# sp6641-aek.net
KiCad netlist of a schematic drawn in EAGLE
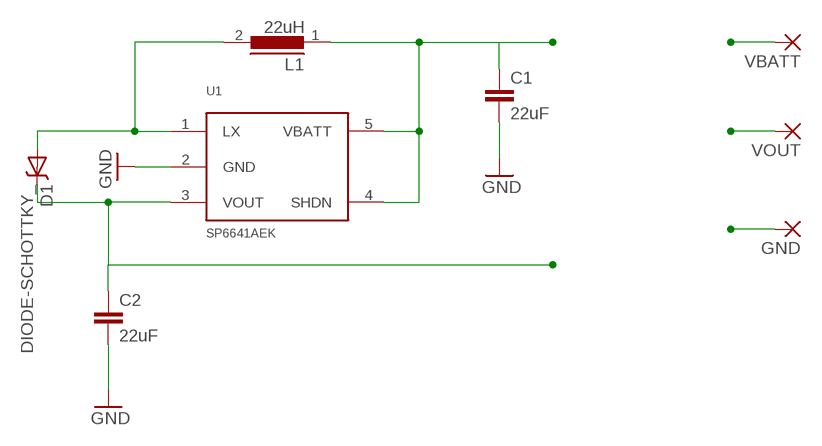
[diagram p0: schematic, sheet 1]

(export (version "E")
  (design (tool "Eeschema 10.0.6"))
  (components
    (comp (ref "C1")
      (value "22uF")
      (footprint "eagle-import:1206")
      (libsource (lib "eagle-import") (part "CAP1206"))
    )
    (comp (ref "C2")
      (value "22uF")
      (footprint "eagle-import:1206")
      (libsource (lib "eagle-import") (part "CAP1206"))
    )
    (comp (ref "D1")
      (value "DIODE-SCHOTTKY_")
      (footprint "eagle-import:SMA-DIODE")
      (libsource (lib "eagle-import") (part "DIODE-SCHOTTKY_"))
    )
    (comp (ref "GND")
      (value "WIREPADSMD2,54-5,08")
      (footprint "eagle-import:SMD2,54-5,08")
      (libsource (lib "eagle-import") (part "WIREPADSMD2,54-5,08"))
    )
    (comp (ref "L1")
      (value "22uH")
      (footprint "eagle-import:DR73")
      (libsource (lib "eagle-import") (part "DR73"))
    )
    (comp (ref "U1")
      (value "SP6641AEK")
      (footprint "eagle-import:SOT23-5")
      (libsource (lib "eagle-import") (part "SP6641SP6641A/B"))
    )
    (comp (ref "VBATT")
      (value "WIREPADSMD2,54-5,08")
      (footprint "eagle-import:SMD2,54-5,08")
      (libsource (lib "eagle-import") (part "WIREPADSMD2,54-5,08"))
    )
    (comp (ref "VOUT")
      (value "WIREPADSMD2,54-5,08")
      (footprint "eagle-import:SMD2,54-5,08")
      (libsource (lib "eagle-import") (part "WIREPADSMD2,54-5,08"))
    )
  )
  (nets
    (net (code "1") (name "/VBATT") (class "Default")
      (node (ref "C1") (pin "1") (pinfunction "1_1") (pintype "passive"))
      (node (ref "L1") (pin "1") (pinfunction "1_1") (pintype "passive"))
      (node (ref "U1") (pin "4") (pinfunction "SHDN_4") (pintype "bidirectional"))
      (node (ref "U1") (pin "5") (pinfunction "VBATT_5") (pintype "bidirectional"))
      (node (ref "VBATT") (pin "1") (pinfunction "P_1") (pintype "passive"))
    )
    (net (code "2") (name "/VOUT") (class "Default")
      (node (ref "C2") (pin "1") (pinfunction "1_1") (pintype "passive"))
      (node (ref "D1") (pin "C") (pinfunction "C_C") (pintype "passive"))
      (node (ref "U1") (pin "3") (pinfunction "VOUT_3") (pintype "bidirectional"))
      (node (ref "VOUT") (pin "1") (pinfunction "P_1") (pintype "passive"))
    )
    (net (code "3") (name "GND") (class "Default")
      (node (ref "C1") (pin "2") (pinfunction "2_2") (pintype "passive"))
      (node (ref "C2") (pin "2") (pinfunction "2_2") (pintype "passive"))
      (node (ref "GND") (pin "1") (pinfunction "P_1") (pintype "passive"))
      (node (ref "U1") (pin "2") (pinfunction "GND_2") (pintype "bidirectional"))
    )
    (net (code "4") (name "Net-(U1-LX)") (class "Default")
      (node (ref "D1") (pin "A") (pinfunction "A_A") (pintype "passive"))
      (node (ref "L1") (pin "2") (pinfunction "2_2") (pintype "passive"))
      (node (ref "U1") (pin "1") (pinfunction "LX_1") (pintype "bidirectional"))
    )
  )
)
